# debug_board.net
KiCad netlist of a schematic drawn in Altium Designer
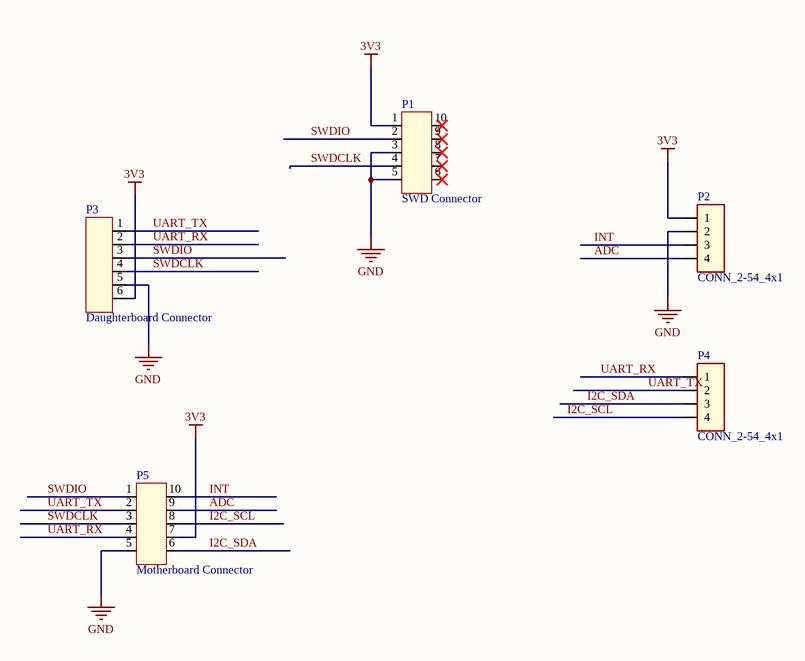
[diagram p0: debug_board.SchDoc]

(export (version "E")
  (design (tool "Eeschema 10.0.6"))
  (components
    (comp (ref "P1")
      (value "SWD Connector")
      (footprint "1_27-5x2 Female Right Angle")
      (description "1.27mm pitch 5x2 pin male connector")
      (libsource (lib "thesis_schem_lib") (part "CONN_1-27_5x2"))
    )
    (comp (ref "P2")
      (value "CONN_2-54_4x1")
      (footprint "2_54-4x1_FEMALE_HEADER_THT")
      (libsource (lib "thesis_schem_lib") (part "CONN_2-54_4x1"))
    )
    (comp (ref "P3")
      (value "Daughterboard Connector")
      (footprint "1_27-6x1-MALE_HEADER_RIGHT_THT")
      (libsource (lib "thesis_schem_lib") (part "CONN_1-26_6x1"))
    )
    (comp (ref "P4")
      (value "CONN_2-54_4x1")
      (footprint "2_54-4x1_FEMALE_HEADER_THT")
      (libsource (lib "thesis_schem_lib") (part "CONN_2-54_4x1"))
    )
    (comp (ref "P5")
      (value "Motherboard Connector")
      (footprint "1_27-5x2 Female Right Angle")
      (description "1.27mm pitch 5x2 pin male connector")
      (libsource (lib "thesis_schem_lib") (part "CONN_1-27_5x2"))
    )
  )
  (nets
    (net (code "1") (name "/ADC") (class "Default")
      (node (ref "P2") (pin "4") (pinfunction "4_4") (pintype "passive"))
      (node (ref "P5") (pin "9") (pintype "passive"))
    )
    (net (code "2") (name "/I2C_SCL") (class "Default")
      (node (ref "P4") (pin "4") (pinfunction "4_4") (pintype "passive"))
      (node (ref "P5") (pin "8") (pintype "passive"))
    )
    (net (code "3") (name "/I2C_SDA") (class "Default")
      (node (ref "P4") (pin "3") (pinfunction "3_3") (pintype "passive"))
      (node (ref "P5") (pin "6") (pintype "passive"))
    )
    (net (code "4") (name "/INT") (class "Default")
      (node (ref "P2") (pin "3") (pinfunction "3_3") (pintype "passive"))
      (node (ref "P5") (pin "10") (pintype "passive"))
    )
    (net (code "5") (name "/SWDCLK") (class "Default")
      (node (ref "P1") (pin "4") (pintype "passive"))
      (node (ref "P3") (pin "4") (pintype "passive"))
      (node (ref "P5") (pin "3") (pintype "passive"))
    )
    (net (code "6") (name "/SWDIO") (class "Default")
      (node (ref "P1") (pin "2") (pintype "passive"))
      (node (ref "P3") (pin "3") (pintype "passive"))
      (node (ref "P5") (pin "1") (pintype "passive"))
    )
    (net (code "7") (name "/UART_RX") (class "Default")
      (node (ref "P3") (pin "2") (pintype "passive"))
      (node (ref "P4") (pin "1") (pinfunction "1_1") (pintype "passive"))
      (node (ref "P5") (pin "4") (pintype "passive"))
    )
    (net (code "8") (name "/UART_TX") (class "Default")
      (node (ref "P3") (pin "1") (pintype "passive"))
      (node (ref "P4") (pin "2") (pinfunction "2_2") (pintype "passive"))
      (node (ref "P5") (pin "2") (pintype "passive"))
    )
    (net (code "9") (name "3V3") (class "Default")
      (node (ref "P1") (pin "1") (pintype "passive"))
      (node (ref "P2") (pin "1") (pinfunction "1_1") (pintype "passive"))
      (node (ref "P3") (pin "6") (pintype "passive"))
      (node (ref "P5") (pin "7") (pintype "passive"))
    )
    (net (code "10") (name "GND") (class "Default")
      (node (ref "P1") (pin "3") (pintype "passive"))
      (node (ref "P1") (pin "5") (pintype "passive"))
      (node (ref "P2") (pin "2") (pinfunction "2_2") (pintype "passive"))
      (node (ref "P3") (pin "5") (pintype "passive"))
      (node (ref "P5") (pin "5") (pintype "passive"))
    )
    (net (code "11") (name "unconnected-(P1-Pad6)") (class "Default")
      (node (ref "P1") (pin "6") (pintype "passive+no_connect"))
    )
    (net (code "12") (name "unconnected-(P1-Pad7)") (class "Default")
      (node (ref "P1") (pin "7") (pintype "passive+no_connect"))
    )
    (net (code "13") (name "unconnected-(P1-Pad8)") (class "Default")
      (node (ref "P1") (pin "8") (pintype "passive+no_connect"))
    )
    (net (code "14") (name "unconnected-(P1-Pad9)") (class "Default")
      (node (ref "P1") (pin "9") (pintype "passive+no_connect"))
    )
    (net (code "15") (name "unconnected-(P1-Pad10)") (class "Default")
      (node (ref "P1") (pin "10") (pintype "passive+no_connect"))
    )
  )
)
